# EPGinput.net
KiCad netlist of a schematic drawn in EAGLE
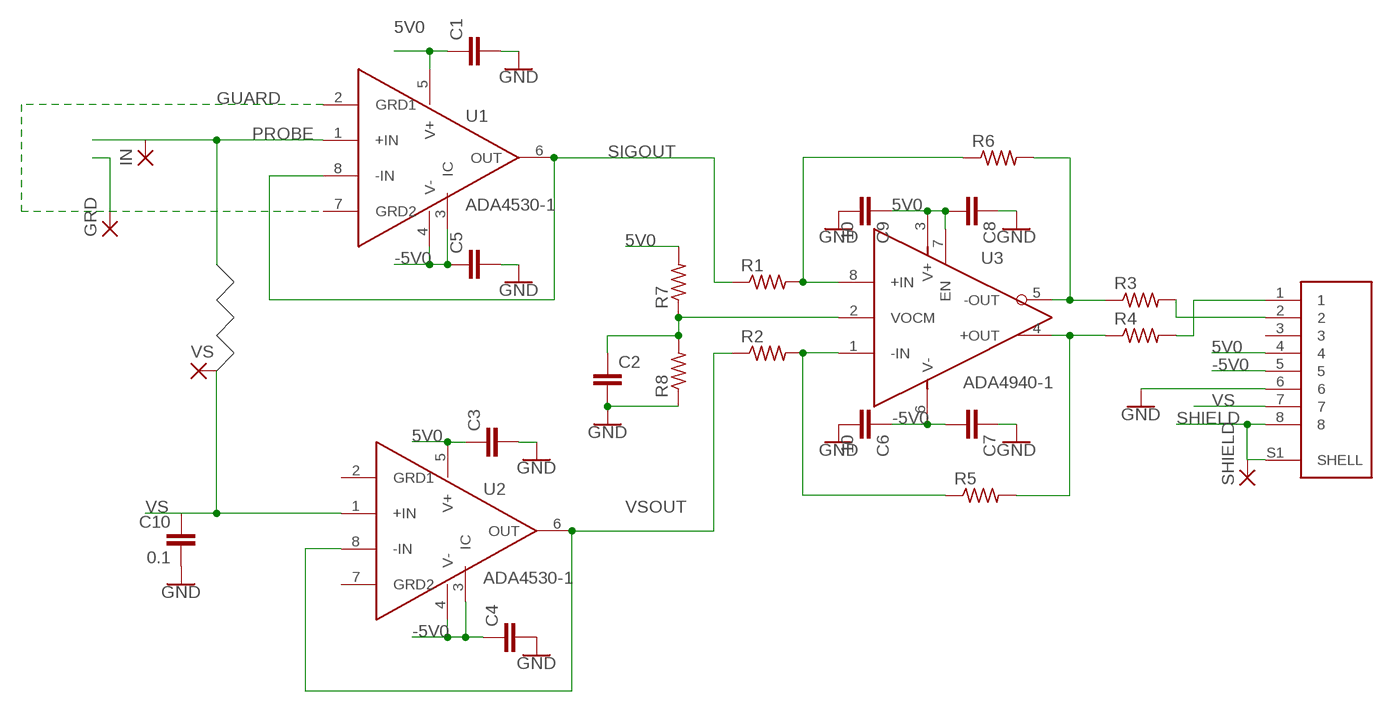
[diagram p0: schematic, sheet 1]

(export (version "E")
  (design (tool "Eeschema 10.0.6"))
  (components
    (comp (ref "C1")
      (value "CAPS0603S")
      (footprint "eagle-import:0603S")
      (libsource (lib "eagle-import") (part "CAPS0603S"))
    )
    (comp (ref "C2")
      (value "CAPS0603S")
      (footprint "eagle-import:0603S")
      (libsource (lib "eagle-import") (part "CAPS0603S"))
    )
    (comp (ref "C3")
      (value "CAPS0603S")
      (footprint "eagle-import:0603S")
      (libsource (lib "eagle-import") (part "CAPS0603S"))
    )
    (comp (ref "C4")
      (value "CAPS0603S")
      (footprint "eagle-import:0603S")
      (libsource (lib "eagle-import") (part "CAPS0603S"))
    )
    (comp (ref "C5")
      (value "CAPS0603S")
      (footprint "eagle-import:0603S")
      (libsource (lib "eagle-import") (part "CAPS0603S"))
    )
    (comp (ref "C6")
      (value "10")
      (footprint "eagle-import:1206S")
      (libsource (lib "eagle-import") (part "CAPS1206S"))
    )
    (comp (ref "C7")
      (value "CAPS0603S")
      (footprint "eagle-import:0603S")
      (libsource (lib "eagle-import") (part "CAPS0603S"))
    )
    (comp (ref "C8")
      (value "CAPS0603S")
      (footprint "eagle-import:0603S")
      (libsource (lib "eagle-import") (part "CAPS0603S"))
    )
    (comp (ref "C9")
      (value "10")
      (footprint "eagle-import:1206S")
      (libsource (lib "eagle-import") (part "CAPS1206S"))
    )
    (comp (ref "C10")
      (value "0.1")
      (footprint "eagle-import:0603S")
      (libsource (lib "eagle-import") (part "CAPS0603S"))
    )
    (comp (ref "GRD")
      (value "2,15/1,0")
      (footprint "eagle-import:2,15_1,0")
      (libsource (lib "eagle-import") (part "2,15/1,0"))
    )
    (comp (ref "IN")
      (value "SMD2")
      (footprint "eagle-import:SMD1,27-2,54")
      (libsource (lib "eagle-import") (part "SMD2"))
    )
    (comp (ref "J1")
      (value "54-00248")
      (footprint "eagle-import:TENSILITY_54-00248")
      (libsource (lib "eagle-import") (part "54-00248"))
    )
    (comp (ref "R1")
      (value "RESISTOR_SM0805S")
      (footprint "eagle-import:0805S")
      (libsource (lib "eagle-import") (part "RESISTOR_SM0805S"))
    )
    (comp (ref "R2")
      (value "RESISTOR_SM0805S")
      (footprint "eagle-import:0805S")
      (libsource (lib "eagle-import") (part "RESISTOR_SM0805S"))
    )
    (comp (ref "R3")
      (value "RESISTOR_SM0805S")
      (footprint "eagle-import:0805S")
      (libsource (lib "eagle-import") (part "RESISTOR_SM0805S"))
    )
    (comp (ref "R4")
      (value "RESISTOR_SM0805S")
      (footprint "eagle-import:0805S")
      (libsource (lib "eagle-import") (part "RESISTOR_SM0805S"))
    )
    (comp (ref "R5")
      (value "RESISTOR_SM0805S")
      (footprint "eagle-import:0805S")
      (libsource (lib "eagle-import") (part "RESISTOR_SM0805S"))
    )
    (comp (ref "R6")
      (value "RESISTOR_SM0805S")
      (footprint "eagle-import:0805S")
      (libsource (lib "eagle-import") (part "RESISTOR_SM0805S"))
    )
    (comp (ref "R7")
      (value "RESISTOR_SM0805S")
      (footprint "eagle-import:0805S")
      (libsource (lib "eagle-import") (part "RESISTOR_SM0805S"))
    )
    (comp (ref "R8")
      (value "RESISTOR_SM0805S")
      (footprint "eagle-import:0805S")
      (libsource (lib "eagle-import") (part "RESISTOR_SM0805S"))
    )
    (comp (ref "SHIELD")
      (value "2,15/1,0")
      (footprint "eagle-import:2,15_1,0")
      (libsource (lib "eagle-import") (part "2,15/1,0"))
    )
    (comp (ref "U1")
      (value "ADA4530-1")
      (footprint "eagle-import:SOIC-8")
      (libsource (lib "eagle-import") (part "ADA4530-1"))
    )
    (comp (ref "U2")
      (value "ADA4530-1")
      (footprint "eagle-import:SOIC-8")
      (libsource (lib "eagle-import") (part "ADA4530-1"))
    )
    (comp (ref "U3")
      (value "ADA4940-1")
      (footprint "eagle-import:SOIC-8")
      (libsource (lib "eagle-import") (part "ADA4940-1"))
    )
    (comp (ref "VS")
      (value "2,15/1,0")
      (footprint "eagle-import:2,15_1,0")
      (libsource (lib "eagle-import") (part "2,15/1,0"))
    )
  )
  (nets
    (net (code "1") (name "/-5V0") (class "Default")
      (node (ref "C4") (pin "1") (pinfunction "1_1") (pintype "passive"))
      (node (ref "C5") (pin "1") (pinfunction "1_1") (pintype "passive"))
      (node (ref "C6") (pin "1") (pinfunction "1_1") (pintype "passive"))
      (node (ref "C7") (pin "2") (pinfunction "2_2") (pintype "passive"))
      (node (ref "J1") (pin "5") (pinfunction "5_5") (pintype "bidirectional"))
      (node (ref "U1") (pin "3") (pinfunction "IC_3") (pintype "bidirectional"))
      (node (ref "U1") (pin "4") (pinfunction "V-_4") (pintype "bidirectional"))
      (node (ref "U2") (pin "3") (pinfunction "IC_3") (pintype "bidirectional"))
      (node (ref "U2") (pin "4") (pinfunction "V-_4") (pintype "bidirectional"))
      (node (ref "U3") (pin "6") (pinfunction "V-_6") (pintype "bidirectional"))
    )
    (net (code "2") (name "/5V0") (class "Default")
      (node (ref "C1") (pin "1") (pinfunction "1_1") (pintype "passive"))
      (node (ref "C3") (pin "1") (pinfunction "1_1") (pintype "passive"))
      (node (ref "C8") (pin "2") (pinfunction "2_2") (pintype "passive"))
      (node (ref "C9") (pin "1") (pinfunction "1_1") (pintype "passive"))
      (node (ref "J1") (pin "4") (pinfunction "4_4") (pintype "bidirectional"))
      (node (ref "R7") (pin "2") (pinfunction "2_2") (pintype "passive"))
      (node (ref "U1") (pin "5") (pinfunction "V+_5") (pintype "bidirectional"))
      (node (ref "U2") (pin "5") (pinfunction "V+_5") (pintype "bidirectional"))
      (node (ref "U3") (pin "3") (pinfunction "V+_3") (pintype "bidirectional"))
      (node (ref "U3") (pin "7") (pinfunction "EN_7") (pintype "bidirectional"))
    )
    (net (code "3") (name "/GUARD") (class "Default")
      (node (ref "GRD") (pin "1") (pinfunction "P_1") (pintype "passive"))
      (node (ref "U1") (pin "2") (pinfunction "GRD1_2") (pintype "bidirectional"))
      (node (ref "U1") (pin "7") (pinfunction "GRD2_7") (pintype "bidirectional"))
    )
    (net (code "4") (name "/PROBE") (class "Default")
      (node (ref "IN") (pin "1") (pinfunction "P_1") (pintype "passive"))
      (node (ref "U1") (pin "1") (pinfunction "+IN_1") (pintype "bidirectional"))
    )
    (net (code "5") (name "/SHIELD") (class "Default")
      (node (ref "J1") (pin "8") (pinfunction "8_8") (pintype "bidirectional"))
      (node (ref "J1") (pin "S1") (pinfunction "SHELL_S1") (pintype "bidirectional"))
      (node (ref "SHIELD") (pin "1") (pinfunction "P_1") (pintype "passive"))
    )
    (net (code "6") (name "/SIGOUT") (class "Default")
      (node (ref "R1") (pin "1") (pinfunction "1_1") (pintype "passive"))
      (node (ref "U1") (pin "6") (pinfunction "OUT_6") (pintype "bidirectional"))
      (node (ref "U1") (pin "8") (pinfunction "-IN_8") (pintype "bidirectional"))
    )
    (net (code "7") (name "/VS") (class "Default")
      (node (ref "C10") (pin "1") (pinfunction "1_1") (pintype "passive"))
      (node (ref "J1") (pin "7") (pinfunction "7_7") (pintype "bidirectional"))
      (node (ref "U2") (pin "1") (pinfunction "+IN_1") (pintype "bidirectional"))
      (node (ref "VS") (pin "1") (pinfunction "P_1") (pintype "passive"))
    )
    (net (code "8") (name "/VSOUT") (class "Default")
      (node (ref "R2") (pin "1") (pinfunction "1_1") (pintype "passive"))
      (node (ref "U2") (pin "6") (pinfunction "OUT_6") (pintype "bidirectional"))
      (node (ref "U2") (pin "8") (pinfunction "-IN_8") (pintype "bidirectional"))
    )
    (net (code "9") (name "GND") (class "Default")
      (node (ref "C1") (pin "2") (pinfunction "2_2") (pintype "passive"))
      (node (ref "C10") (pin "2") (pinfunction "2_2") (pintype "passive"))
      (node (ref "C2") (pin "2") (pinfunction "2_2") (pintype "passive"))
      (node (ref "C3") (pin "2") (pinfunction "2_2") (pintype "passive"))
      (node (ref "C4") (pin "2") (pinfunction "2_2") (pintype "passive"))
      (node (ref "C5") (pin "2") (pinfunction "2_2") (pintype "passive"))
      (node (ref "C6") (pin "2") (pinfunction "2_2") (pintype "passive"))
      (node (ref "C7") (pin "1") (pinfunction "1_1") (pintype "passive"))
      (node (ref "C8") (pin "1") (pinfunction "1_1") (pintype "passive"))
      (node (ref "C9") (pin "2") (pinfunction "2_2") (pintype "passive"))
      (node (ref "J1") (pin "6") (pinfunction "6_6") (pintype "bidirectional"))
      (node (ref "R8") (pin "1") (pinfunction "1_1") (pintype "passive"))
    )
    (net (code "10") (name "Net-(J1-Pad1)") (class "Default")
      (node (ref "J1") (pin "1") (pinfunction "1_1") (pintype "bidirectional"))
      (node (ref "R4") (pin "2") (pinfunction "2_2") (pintype "passive"))
    )
    (net (code "11") (name "Net-(J1-Pad2)") (class "Default")
      (node (ref "J1") (pin "2") (pinfunction "2_2") (pintype "bidirectional"))
      (node (ref "R3") (pin "2") (pinfunction "2_2") (pintype "passive"))
    )
    (net (code "12") (name "Net-(U3-+IN)") (class "Default")
      (node (ref "R1") (pin "2") (pinfunction "2_2") (pintype "passive"))
      (node (ref "R6") (pin "1") (pinfunction "1_1") (pintype "passive"))
      (node (ref "U3") (pin "8") (pinfunction "+IN_8") (pintype "bidirectional"))
    )
    (net (code "13") (name "Net-(U3-+OUT)") (class "Default")
      (node (ref "R4") (pin "1") (pinfunction "1_1") (pintype "passive"))
      (node (ref "R5") (pin "2") (pinfunction "2_2") (pintype "passive"))
      (node (ref "U3") (pin "4") (pinfunction "+OUT_4") (pintype "bidirectional"))
    )
    (net (code "14") (name "Net-(U3--IN)") (class "Default")
      (node (ref "R2") (pin "2") (pinfunction "2_2") (pintype "passive"))
      (node (ref "R5") (pin "1") (pinfunction "1_1") (pintype "passive"))
      (node (ref "U3") (pin "1") (pinfunction "-IN_1") (pintype "bidirectional"))
    )
    (net (code "15") (name "Net-(U3--OUT)") (class "Default")
      (node (ref "R3") (pin "1") (pinfunction "1_1") (pintype "passive"))
      (node (ref "R6") (pin "2") (pinfunction "2_2") (pintype "passive"))
      (node (ref "U3") (pin "5") (pinfunction "-OUT_5") (pintype "bidirectional"))
    )
    (net (code "16") (name "Net-(U3-VOCM)") (class "Default")
      (node (ref "C2") (pin "1") (pinfunction "1_1") (pintype "passive"))
      (node (ref "R7") (pin "1") (pinfunction "1_1") (pintype "passive"))
      (node (ref "R8") (pin "2") (pinfunction "2_2") (pintype "passive"))
      (node (ref "U3") (pin "2") (pinfunction "VOCM_2") (pintype "bidirectional"))
    )
    (net (code "17") (name "unconnected-(J1-Pad3)") (class "Default")
      (node (ref "J1") (pin "3") (pinfunction "3_3") (pintype "bidirectional"))
    )
    (net (code "18") (name "unconnected-(U2-GRD1-Pad2)") (class "Default")
      (node (ref "U2") (pin "2") (pinfunction "GRD1_2") (pintype "bidirectional"))
    )
    (net (code "19") (name "unconnected-(U2-GRD2-Pad7)") (class "Default")
      (node (ref "U2") (pin "7") (pinfunction "GRD2_7") (pintype "bidirectional"))
    )
  )
)
